# working.net
KiCad netlist of a schematic drawn in EAGLE
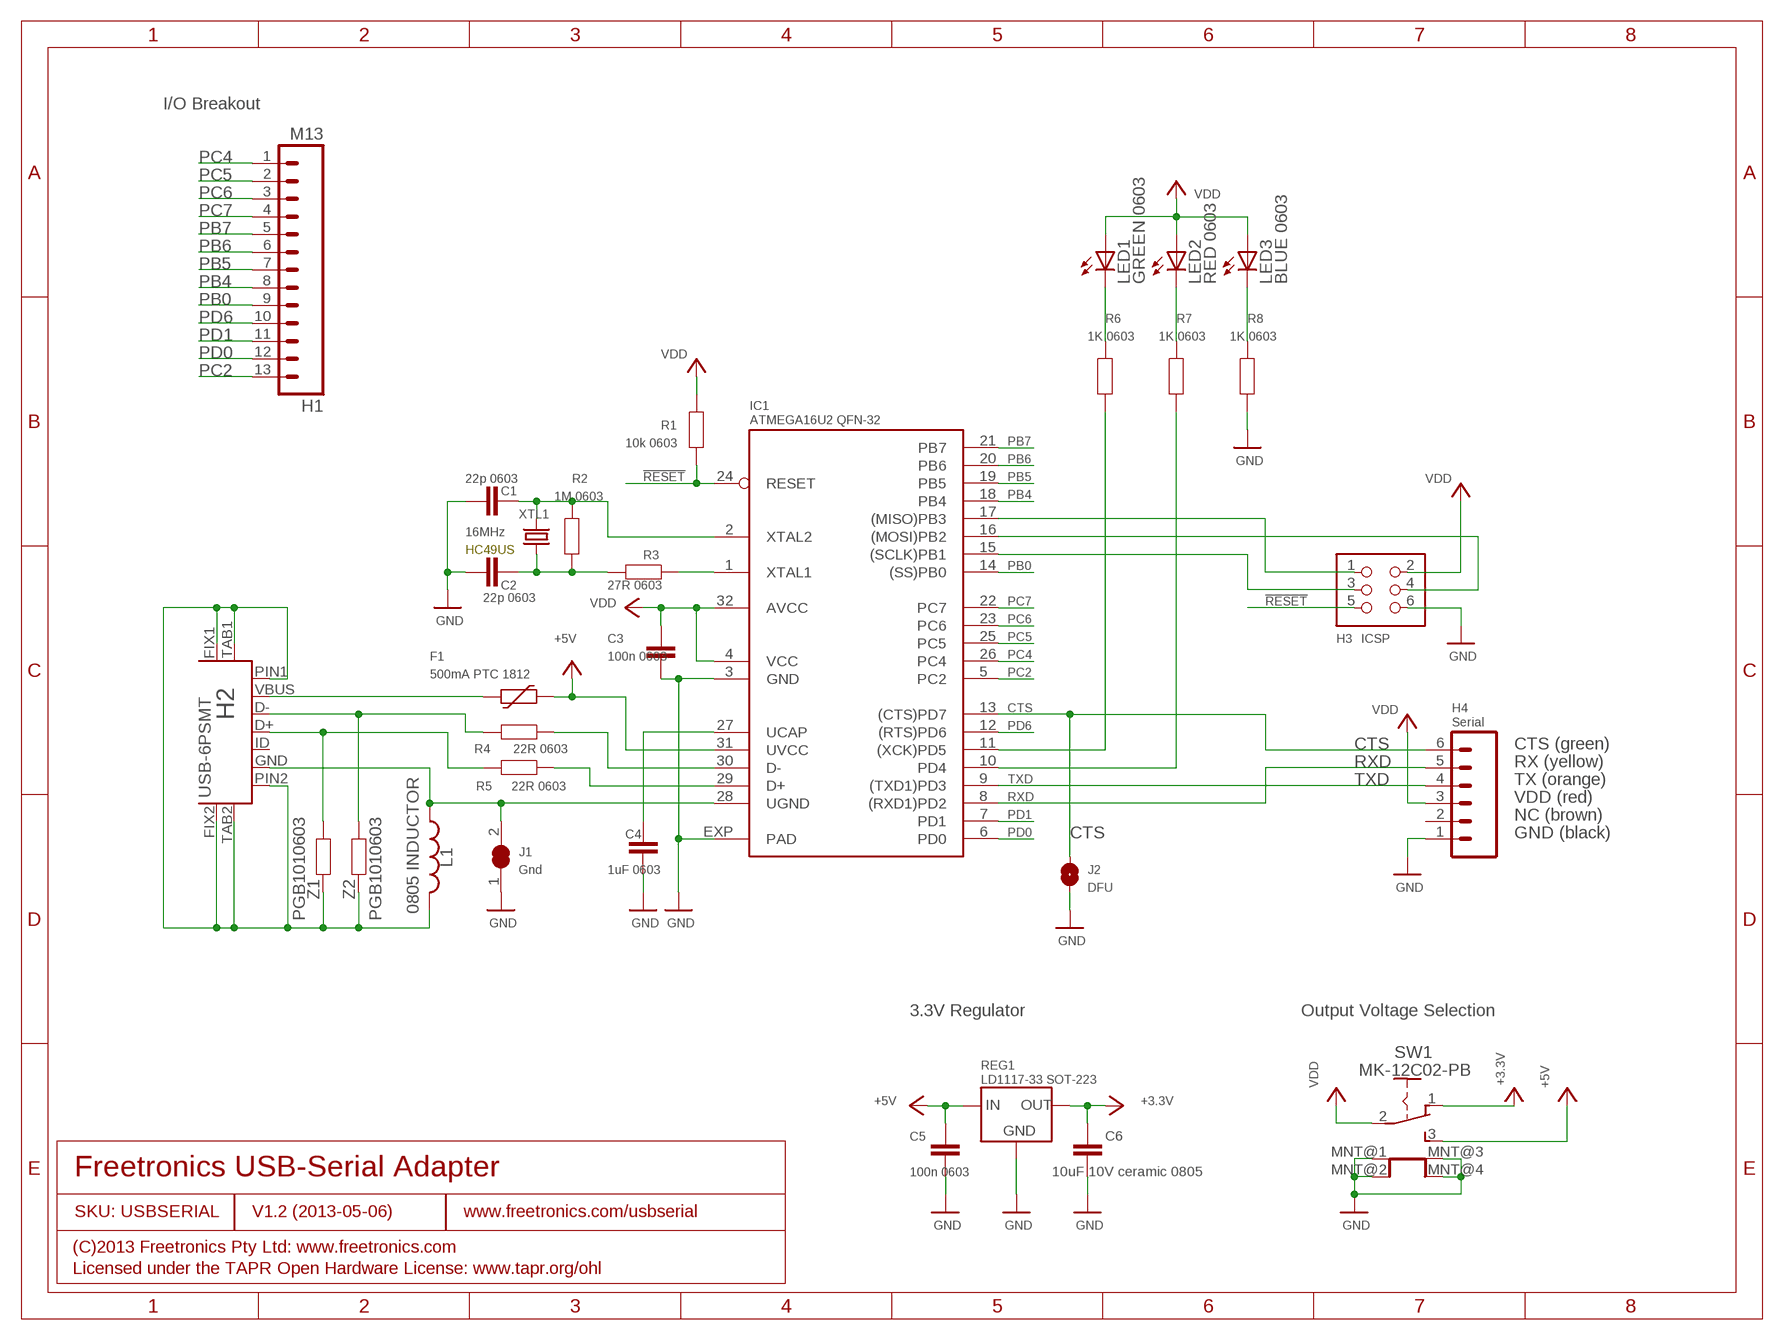
[diagram p0: schematic, sheet 1]

(export (version "E")
  (design (tool "Eeschema 10.0.6"))
  (components
    (comp (ref "C1")
      (value "22p 0603")
      (footprint "eagle-import:0603")
      (libsource (lib "eagle-import") (part "CAP0603"))
    )
    (comp (ref "C2")
      (value "22p 0603")
      (footprint "eagle-import:0603")
      (libsource (lib "eagle-import") (part "CAP0603"))
    )
    (comp (ref "C3")
      (value "100n 0603")
      (footprint "eagle-import:0603")
      (libsource (lib "eagle-import") (part "CAP0603"))
    )
    (comp (ref "C4")
      (value "1uF 0603")
      (footprint "eagle-import:0603")
      (libsource (lib "eagle-import") (part "CAP0603"))
    )
    (comp (ref "C5")
      (value "100n 0603")
      (footprint "eagle-import:0603")
      (libsource (lib "eagle-import") (part "CAP0603"))
    )
    (comp (ref "C6")
      (value "10uF 10V ceramic 0805")
      (footprint "eagle-import:C0805")
      (libsource (lib "eagle-import") (part "C-EUC0805"))
    )
    (comp (ref "F1")
      (value "500mA PTC 1812")
      (footprint "eagle-import:1812")
      (libsource (lib "eagle-import") (part "PTC"))
    )
    (comp (ref "H1")
      (value "M13")
      (footprint "eagle-import:1X13")
      (libsource (lib "eagle-import") (part "M13"))
    )
    (comp (ref "H2")
      (value "USB-6PSMT")
      (footprint "eagle-import:USB-MICROB-MB05PMXX")
      (libsource (lib "eagle-import") (part "USB-6PSMT"))
    )
    (comp (ref "H3")
      (value "ICSP")
      (footprint "eagle-import:HEADER_2X3")
      (libsource (lib "eagle-import") (part "HEADER_2X3"))
    )
    (comp (ref "H4")
      (value "Serial")
      (footprint "eagle-import:1X06")
      (libsource (lib "eagle-import") (part "M06SIP"))
    )
    (comp (ref "IC1")
      (value "ATMEGA16U2 QFN-32")
      (footprint "eagle-import:ATMEL_QFN32")
      (libsource (lib "eagle-import") (part "ATMEL_ATMEGA8U2-MUQFN"))
    )
    (comp (ref "J1")
      (value "Gnd")
      (footprint "eagle-import:SJC")
      (libsource (lib "eagle-import") (part "SJCN"))
    )
    (comp (ref "J2") (value "DFU") (footprint "eagle-import:SJ") (libsource (lib "eagle-import") (part "SJ")))
    (comp (ref "L1")
      (value "0805 INDUCTOR")
      (footprint "eagle-import:0805-LARGE")
      (libsource (lib "eagle-import") (part "INDUCTOR0805-LARGE"))
    )
    (comp (ref "LED1")
      (value "GREEN 0603")
      (footprint "eagle-import:LED-0603")
      (libsource (lib "eagle-import") (part "LED0603"))
    )
    (comp (ref "LED2")
      (value "RED 0603")
      (footprint "eagle-import:LED-0603")
      (libsource (lib "eagle-import") (part "LED0603"))
    )
    (comp (ref "LED3")
      (value "BLUE 0603")
      (footprint "eagle-import:LED-0603")
      (libsource (lib "eagle-import") (part "LED0603"))
    )
    (comp (ref "R1")
      (value "10k 0603")
      (footprint "eagle-import:0603")
      (libsource (lib "eagle-import") (part "RESISTOR0603"))
    )
    (comp (ref "R2")
      (value "1M 0603")
      (footprint "eagle-import:0603")
      (libsource (lib "eagle-import") (part "RESISTOR0603"))
    )
    (comp (ref "R3")
      (value "27R 0603")
      (footprint "eagle-import:0603")
      (libsource (lib "eagle-import") (part "RESISTOR0603"))
    )
    (comp (ref "R4")
      (value "22R 0603")
      (footprint "eagle-import:0603")
      (libsource (lib "eagle-import") (part "RESISTOR0603"))
    )
    (comp (ref "R5")
      (value "22R 0603")
      (footprint "eagle-import:0603")
      (libsource (lib "eagle-import") (part "RESISTOR0603"))
    )
    (comp (ref "R6")
      (value "1K 0603")
      (footprint "eagle-import:0603")
      (libsource (lib "eagle-import") (part "RESISTOR0603"))
    )
    (comp (ref "R7")
      (value "1K 0603")
      (footprint "eagle-import:0603")
      (libsource (lib "eagle-import") (part "RESISTOR0603"))
    )
    (comp (ref "R8")
      (value "1K 0603")
      (footprint "eagle-import:0603")
      (libsource (lib "eagle-import") (part "RESISTOR0603"))
    )
    (comp (ref "REG1")
      (value "LD1117-33 SOT-223")
      (footprint "eagle-import:SOT-223")
      (libsource (lib "eagle-import") (part "LD1117-FIXED"))
    )
    (comp (ref "SW1")
      (value "MK-12C02-PB")
      (footprint "eagle-import:MK-12C02")
      (libsource (lib "eagle-import") (part "SWITCH-SPDT-4TABSSMT"))
    )
    (comp (ref "XTL1")
      (value "16MHz")
      (footprint "eagle-import:HC49U-V")
      (libsource (lib "eagle-import") (part "CRYSTALHC49UV"))
    )
    (comp (ref "Z1")
      (value "PGB1010603")
      (footprint "eagle-import:0603")
      (libsource (lib "eagle-import") (part "RESISTOR0603"))
    )
    (comp (ref "Z2")
      (value "PGB1010603")
      (footprint "eagle-import:0603")
      (libsource (lib "eagle-import") (part "RESISTOR0603"))
    )
  )
  (nets
    (net (code "1") (name "+3.3V") (class "Default")
      (node (ref "C6") (pin "1") (pinfunction "1_1") (pintype "passive"))
      (node (ref "REG1") (pin "2") (pinfunction "OUT_2") (pintype "power_in"))
      (node (ref "REG1") (pin "4") (pinfunction "OUT_4") (pintype "power_in"))
      (node (ref "SW1") (pin "1") (pinfunction "A_1") (pintype "passive"))
    )
    (net (code "2") (name "+5V") (class "Default")
      (node (ref "C5") (pin "1") (pinfunction "1_1") (pintype "passive"))
      (node (ref "F1") (pin "2") (pinfunction "P$2_2") (pintype "bidirectional"))
      (node (ref "IC1") (pin "31") (pinfunction "UVCC_31") (pintype "power_in"))
      (node (ref "REG1") (pin "3") (pinfunction "IN_3") (pintype "input"))
      (node (ref "SW1") (pin "3") (pinfunction "B_3") (pintype "passive"))
    )
    (net (code "3") (name "/CTS") (class "Default")
      (node (ref "H4") (pin "6") (pinfunction "6_6") (pintype "passive"))
      (node (ref "IC1") (pin "13") (pinfunction "(CTS)PD7_13") (pintype "bidirectional"))
      (node (ref "J2") (pin "2") (pinfunction "2_2") (pintype "passive"))
    )
    (net (code "4") (name "/PB0") (class "Default")
      (node (ref "H1") (pin "9") (pinfunction "9_9") (pintype "passive"))
      (node (ref "IC1") (pin "14") (pinfunction "(SS)PB0_14") (pintype "bidirectional"))
    )
    (net (code "5") (name "/PB4") (class "Default")
      (node (ref "H1") (pin "8") (pinfunction "8_8") (pintype "passive"))
      (node (ref "IC1") (pin "18") (pinfunction "PB4_18") (pintype "bidirectional"))
    )
    (net (code "6") (name "/PB5") (class "Default")
      (node (ref "H1") (pin "7") (pinfunction "7_7") (pintype "passive"))
      (node (ref "IC1") (pin "19") (pinfunction "PB5_19") (pintype "bidirectional"))
    )
    (net (code "7") (name "/PB6") (class "Default")
      (node (ref "H1") (pin "6") (pinfunction "6_6") (pintype "passive"))
      (node (ref "IC1") (pin "20") (pinfunction "PB6_20") (pintype "bidirectional"))
    )
    (net (code "8") (name "/PB7") (class "Default")
      (node (ref "H1") (pin "5") (pinfunction "5_5") (pintype "passive"))
      (node (ref "IC1") (pin "21") (pinfunction "PB7_21") (pintype "bidirectional"))
    )
    (net (code "9") (name "/PC2") (class "Default")
      (node (ref "H1") (pin "13") (pinfunction "13_13") (pintype "passive"))
      (node (ref "IC1") (pin "5") (pinfunction "PC2_5") (pintype "bidirectional"))
    )
    (net (code "10") (name "/PC4") (class "Default")
      (node (ref "H1") (pin "1") (pinfunction "1_1") (pintype "passive"))
      (node (ref "IC1") (pin "26") (pinfunction "PC4_26") (pintype "bidirectional"))
    )
    (net (code "11") (name "/PC5") (class "Default")
      (node (ref "H1") (pin "2") (pinfunction "2_2") (pintype "passive"))
      (node (ref "IC1") (pin "25") (pinfunction "PC5_25") (pintype "bidirectional"))
    )
    (net (code "12") (name "/PC6") (class "Default")
      (node (ref "H1") (pin "3") (pinfunction "3_3") (pintype "passive"))
      (node (ref "IC1") (pin "23") (pinfunction "PC6_23") (pintype "bidirectional"))
    )
    (net (code "13") (name "/PC7") (class "Default")
      (node (ref "H1") (pin "4") (pinfunction "4_4") (pintype "passive"))
      (node (ref "IC1") (pin "22") (pinfunction "PC7_22") (pintype "bidirectional"))
    )
    (net (code "14") (name "/PD0") (class "Default")
      (node (ref "H1") (pin "12") (pinfunction "12_12") (pintype "passive"))
      (node (ref "IC1") (pin "6") (pinfunction "PD0_6") (pintype "bidirectional"))
    )
    (net (code "15") (name "/PD1") (class "Default")
      (node (ref "H1") (pin "11") (pinfunction "11_11") (pintype "passive"))
      (node (ref "IC1") (pin "7") (pinfunction "PD1_7") (pintype "bidirectional"))
    )
    (net (code "16") (name "/PD6") (class "Default")
      (node (ref "H1") (pin "10") (pinfunction "10_10") (pintype "passive"))
      (node (ref "IC1") (pin "12") (pinfunction "(RTS)PD6_12") (pintype "bidirectional"))
    )
    (net (code "17") (name "/RXD") (class "Default")
      (node (ref "H4") (pin "5") (pinfunction "5_5") (pintype "passive"))
      (node (ref "IC1") (pin "8") (pinfunction "(RXD1)PD2_8") (pintype "bidirectional"))
    )
    (net (code "18") (name "/TXD") (class "Default")
      (node (ref "H4") (pin "4") (pinfunction "4_4") (pintype "passive"))
      (node (ref "IC1") (pin "9") (pinfunction "(TXD1)PD3_9") (pintype "bidirectional"))
    )
    (net (code "19") (name "/~{RESET}") (class "Default")
      (node (ref "H3") (pin "5") (pinfunction "5_5") (pintype "passive"))
      (node (ref "IC1") (pin "24") (pinfunction "RESET_24") (pintype "input"))
      (node (ref "R1") (pin "1") (pinfunction "1_1") (pintype "passive"))
    )
    (net (code "20") (name "GND") (class "Default")
      (node (ref "C1") (pin "1") (pinfunction "1_1") (pintype "passive"))
      (node (ref "C2") (pin "1") (pinfunction "1_1") (pintype "passive"))
      (node (ref "C3") (pin "2") (pinfunction "2_2") (pintype "passive"))
      (node (ref "C4") (pin "2") (pinfunction "2_2") (pintype "passive"))
      (node (ref "C5") (pin "2") (pinfunction "2_2") (pintype "passive"))
      (node (ref "C6") (pin "2") (pinfunction "2_2") (pintype "passive"))
      (node (ref "H3") (pin "6") (pinfunction "6_6") (pintype "passive"))
      (node (ref "H4") (pin "1") (pinfunction "1_1") (pintype "passive"))
      (node (ref "IC1") (pin "3") (pinfunction "GND_3") (pintype "power_in"))
      (node (ref "IC1") (pin "EXP") (pinfunction "PAD_EXP") (pintype "power_in"))
      (node (ref "J1") (pin "1") (pinfunction "1_1") (pintype "passive"))
      (node (ref "J2") (pin "1") (pinfunction "1_1") (pintype "passive"))
      (node (ref "R8") (pin "1") (pinfunction "1_1") (pintype "passive"))
      (node (ref "REG1") (pin "1") (pinfunction "GND_1") (pintype "input"))
      (node (ref "SW1") (pin "MNT@1") (pinfunction "MNT_MNT@1") (pintype "bidirectional"))
      (node (ref "SW1") (pin "MNT@2") (pinfunction "MNT_MNT@2") (pintype "bidirectional"))
      (node (ref "SW1") (pin "MNT@3") (pinfunction "MNT_MNT@3") (pintype "bidirectional"))
      (node (ref "SW1") (pin "MNT@4") (pinfunction "MNT_MNT@4") (pintype "bidirectional"))
    )
    (net (code "21") (name "Net-(C2-Pad2)") (class "Default")
      (node (ref "C2") (pin "2") (pinfunction "2_2") (pintype "passive"))
      (node (ref "R2") (pin "1") (pinfunction "1_1") (pintype "passive"))
      (node (ref "R3") (pin "2") (pinfunction "2_2") (pintype "passive"))
      (node (ref "XTL1") (pin "1") (pinfunction "1_1") (pintype "passive"))
    )
    (net (code "22") (name "Net-(F1-P$1)") (class "Default")
      (node (ref "F1") (pin "1") (pinfunction "P$1_1") (pintype "bidirectional"))
      (node (ref "H2") (pin "VBUS") (pinfunction "VBUS_VBUS") (pintype "bidirectional"))
    )
    (net (code "23") (name "Net-(H2-PadD+)") (class "Default")
      (node (ref "H2") (pin "D+") (pinfunction "D+_D+") (pintype "bidirectional"))
      (node (ref "R5") (pin "2") (pinfunction "2_2") (pintype "passive"))
      (node (ref "Z1") (pin "1") (pinfunction "1_1") (pintype "passive"))
    )
    (net (code "24") (name "Net-(H2-PadD-)") (class "Default")
      (node (ref "H2") (pin "D-") (pinfunction "D-_D-") (pintype "bidirectional"))
      (node (ref "R4") (pin "2") (pinfunction "2_2") (pintype "passive"))
      (node (ref "Z2") (pin "1") (pinfunction "1_1") (pintype "passive"))
    )
    (net (code "25") (name "Net-(H2-PadFIX1)") (class "Default")
      (node (ref "H2") (pin "FIX1") (pinfunction "FIX1_FIX1") (pintype "bidirectional"))
      (node (ref "H2") (pin "FIX2") (pinfunction "FIX2_FIX2") (pintype "bidirectional"))
      (node (ref "H2") (pin "PIN1") (pinfunction "PIN1_PIN1") (pintype "bidirectional"))
      (node (ref "H2") (pin "PIN2") (pinfunction "PIN2_PIN2") (pintype "bidirectional"))
      (node (ref "H2") (pin "TAB1") (pinfunction "TAB1_TAB1") (pintype "bidirectional"))
      (node (ref "H2") (pin "TAB2") (pinfunction "TAB2_TAB2") (pintype "bidirectional"))
      (node (ref "L1") (pin "2") (pinfunction "2_2") (pintype "passive"))
      (node (ref "Z1") (pin "2") (pinfunction "2_2") (pintype "passive"))
      (node (ref "Z2") (pin "2") (pinfunction "2_2") (pintype "passive"))
    )
    (net (code "26") (name "Net-(IC1-(MISO)PB3)") (class "Default")
      (node (ref "H3") (pin "1") (pinfunction "1_1") (pintype "passive"))
      (node (ref "IC1") (pin "17") (pinfunction "(MISO)PB3_17") (pintype "bidirectional"))
    )
    (net (code "27") (name "Net-(IC1-(MOSI)PB2)") (class "Default")
      (node (ref "H3") (pin "4") (pinfunction "4_4") (pintype "passive"))
      (node (ref "IC1") (pin "16") (pinfunction "(MOSI)PB2_16") (pintype "bidirectional"))
    )
    (net (code "28") (name "Net-(IC1-(SCLK)PB1)") (class "Default")
      (node (ref "H3") (pin "3") (pinfunction "3_3") (pintype "passive"))
      (node (ref "IC1") (pin "15") (pinfunction "(SCLK)PB1_15") (pintype "bidirectional"))
    )
    (net (code "29") (name "Net-(IC1-(XCK)PD5)") (class "Default")
      (node (ref "IC1") (pin "11") (pinfunction "(XCK)PD5_11") (pintype "bidirectional"))
      (node (ref "R6") (pin "1") (pinfunction "1_1") (pintype "passive"))
    )
    (net (code "30") (name "Net-(IC1-D+)") (class "Default")
      (node (ref "IC1") (pin "29") (pinfunction "D+_29") (pintype "bidirectional"))
      (node (ref "R5") (pin "1") (pinfunction "1_1") (pintype "passive"))
    )
    (net (code "31") (name "Net-(IC1-D-)") (class "Default")
      (node (ref "IC1") (pin "30") (pinfunction "D-_30") (pintype "bidirectional"))
      (node (ref "R4") (pin "1") (pinfunction "1_1") (pintype "passive"))
    )
    (net (code "32") (name "Net-(IC1-PD4)") (class "Default")
      (node (ref "IC1") (pin "10") (pinfunction "PD4_10") (pintype "bidirectional"))
      (node (ref "R7") (pin "1") (pinfunction "1_1") (pintype "passive"))
    )
    (net (code "33") (name "Net-(IC1-UCAP)") (class "Default")
      (node (ref "C4") (pin "1") (pinfunction "1_1") (pintype "passive"))
      (node (ref "IC1") (pin "27") (pinfunction "UCAP_27") (pintype "passive"))
    )
    (net (code "34") (name "Net-(IC1-UGND)") (class "Default")
      (node (ref "H2") (pin "GND") (pinfunction "GND_GND") (pintype "bidirectional"))
      (node (ref "IC1") (pin "28") (pinfunction "UGND_28") (pintype "power_in"))
      (node (ref "J1") (pin "2") (pinfunction "2_2") (pintype "passive"))
      (node (ref "L1") (pin "1") (pinfunction "1_1") (pintype "passive"))
    )
    (net (code "35") (name "Net-(IC1-XTAL1)") (class "Default")
      (node (ref "IC1") (pin "1") (pinfunction "XTAL1_1") (pintype "bidirectional"))
      (node (ref "R3") (pin "1") (pinfunction "1_1") (pintype "passive"))
    )
    (net (code "36") (name "Net-(IC1-XTAL2)") (class "Default")
      (node (ref "C1") (pin "2") (pinfunction "2_2") (pintype "passive"))
      (node (ref "IC1") (pin "2") (pinfunction "XTAL2_2") (pintype "bidirectional"))
      (node (ref "R2") (pin "2") (pinfunction "2_2") (pintype "passive"))
      (node (ref "XTL1") (pin "2") (pinfunction "2_2") (pintype "passive"))
    )
    (net (code "37") (name "Net-(LED1-PadC)") (class "Default")
      (node (ref "LED1") (pin "C") (pinfunction "C_C") (pintype "passive"))
      (node (ref "R6") (pin "2") (pinfunction "2_2") (pintype "passive"))
    )
    (net (code "38") (name "Net-(LED2-PadC)") (class "Default")
      (node (ref "LED2") (pin "C") (pinfunction "C_C") (pintype "passive"))
      (node (ref "R7") (pin "2") (pinfunction "2_2") (pintype "passive"))
    )
    (net (code "39") (name "Net-(LED3-PadC)") (class "Default")
      (node (ref "LED3") (pin "C") (pinfunction "C_C") (pintype "passive"))
      (node (ref "R8") (pin "2") (pinfunction "2_2") (pintype "passive"))
    )
    (net (code "40") (name "VDD") (class "Default")
      (node (ref "C3") (pin "1") (pinfunction "1_1") (pintype "passive"))
      (node (ref "H3") (pin "2") (pinfunction "2_2") (pintype "passive"))
      (node (ref "H4") (pin "3") (pinfunction "3_3") (pintype "passive"))
      (node (ref "IC1") (pin "32") (pinfunction "AVCC_32") (pintype "power_in"))
      (node (ref "IC1") (pin "4") (pinfunction "VCC_4") (pintype "power_in"))
      (node (ref "LED1") (pin "A") (pinfunction "A_A") (pintype "passive"))
      (node (ref "LED2") (pin "A") (pinfunction "A_A") (pintype "passive"))
      (node (ref "LED3") (pin "A") (pinfunction "A_A") (pintype "passive"))
      (node (ref "R1") (pin "2") (pinfunction "2_2") (pintype "passive"))
      (node (ref "SW1") (pin "2") (pinfunction "COM_2") (pintype "passive"))
    )
    (net (code "41") (name "unconnected-(H2-PadID)") (class "Default")
      (node (ref "H2") (pin "ID") (pinfunction "ID_ID") (pintype "bidirectional"))
    )
    (net (code "42") (name "unconnected-(H4-Pad2)") (class "Default")
      (node (ref "H4") (pin "2") (pinfunction "2_2") (pintype "passive"))
    )
  )
)
